# PowerM.net
KiCad netlist of a schematic drawn in Altium Designer
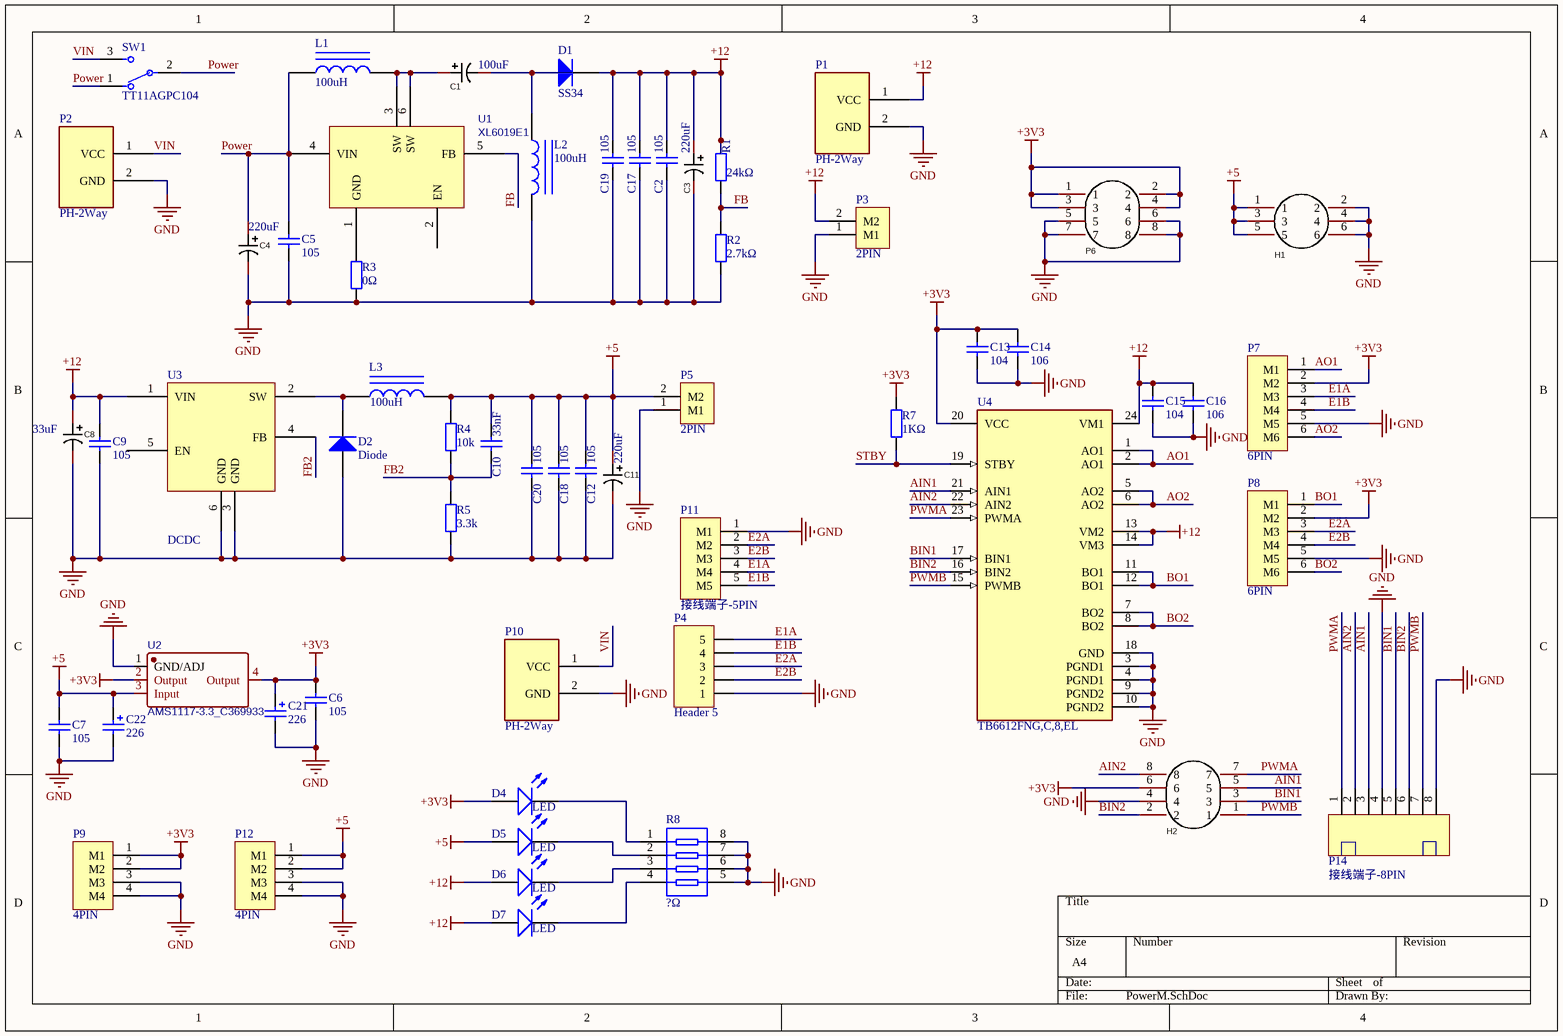
[diagram p0: PowerM.SchDoc]

(export (version "E")
  (design (tool "Eeschema 10.0.6"))
  (components
    (comp (ref "C1")
      (value "100uF")
      (footprint "CAP 5.0*10*12.5")
      (description "插件电容")
      (fields
        (field (name "MANUFACTURER") "MAN YUE(万裕科技)")
        (field (name "MANUFACTURER PART") "ULR107M1CE08TUX0CR")
      )
      (libsource (lib "SFerret") (part "TH_Cap"))
    )
    (comp (ref "C2")
      (value "105")
      (footprint "0603_C")
      (description "贴片电容")
      (libsource (lib "SFerret") (part "SMT_Cap"))
    )
    (comp (ref "C3")
      (value "220uF")
      (footprint "CAP 5.0*10*12.5")
      (description "插件电容")
      (fields
        (field (name "MANUFACTURER") "MAN YUE(万裕科技)")
        (field (name "MANUFACTURER PART") "ULR107M1CE08TUX0CR")
      )
      (libsource (lib "SFerret") (part "TH_Cap"))
    )
    (comp (ref "C4")
      (value "220uF")
      (footprint "CAP 5.0*10*12.5-H")
      (description "插件电容")
      (fields
        (field (name "MANUFACTURER") "MAN YUE(万裕科技)")
        (field (name "MANUFACTURER PART") "ULR107M1CE08TUX0CR")
      )
      (libsource (lib "SFerret") (part "TH_Cap"))
    )
    (comp (ref "C5")
      (value "105")
      (footprint "0603_C")
      (description "贴片电容")
      (libsource (lib "SFerret") (part "SMT_Cap"))
    )
    (comp (ref "C6")
      (value "105")
      (footprint "0603_C")
      (description "贴片电容")
      (libsource (lib "SFerret") (part "SMT_Cap"))
    )
    (comp (ref "C7")
      (value "105")
      (footprint "0603_C")
      (description "贴片电容")
      (libsource (lib "SFerret") (part "SMT_Cap"))
    )
    (comp (ref "C8")
      (value "33uF")
      (footprint "CAP 5.0*10*12.5")
      (description "插件电容")
      (fields
        (field (name "MANUFACTURER") "MAN YUE(万裕科技)")
        (field (name "MANUFACTURER PART") "ULR107M1CE08TUX0CR")
      )
      (libsource (lib "SFerret") (part "TH_Cap"))
    )
    (comp (ref "C9")
      (value "105")
      (footprint "0603_C")
      (description "贴片电容")
      (libsource (lib "SFerret") (part "SMT_Cap"))
    )
    (comp (ref "C10")
      (value "33nF")
      (footprint "0603_C")
      (description "贴片电容")
      (libsource (lib "SFerret") (part "SMT_Cap"))
    )
    (comp (ref "C11")
      (value "220uF")
      (footprint "CAP 5.0*10*12.5-H - GD")
      (description "插件电容")
      (fields
        (field (name "MANUFACTURER") "MAN YUE(万裕科技)")
        (field (name "MANUFACTURER PART") "ULR107M1CE08TUX0CR")
      )
      (libsource (lib "SFerret") (part "TH_Cap"))
    )
    (comp (ref "C12")
      (value "105")
      (footprint "0603_C")
      (description "贴片电容")
      (libsource (lib "SFerret") (part "SMT_Cap"))
    )
    (comp (ref "C13")
      (value "104")
      (footprint "0603_C")
      (description "贴片电容")
      (libsource (lib "SFerret") (part "SMT_Cap"))
    )
    (comp (ref "C14")
      (value "106")
      (footprint "0603_C")
      (description "贴片电容")
      (libsource (lib "SFerret") (part "SMT_Cap"))
    )
    (comp (ref "C15")
      (value "104")
      (footprint "0603_C")
      (description "贴片电容")
      (libsource (lib "SFerret") (part "SMT_Cap"))
    )
    (comp (ref "C16")
      (value "106")
      (footprint "0603_C")
      (description "贴片电容")
      (libsource (lib "SFerret") (part "SMT_Cap"))
    )
    (comp (ref "C17")
      (value "105")
      (footprint "0603_C")
      (description "贴片电容")
      (libsource (lib "SFerret") (part "SMT_Cap"))
    )
    (comp (ref "C18")
      (value "105")
      (footprint "0603_C")
      (description "贴片电容")
      (libsource (lib "SFerret") (part "SMT_Cap"))
    )
    (comp (ref "C19")
      (value "105")
      (footprint "0603_C")
      (description "贴片电容")
      (libsource (lib "SFerret") (part "SMT_Cap"))
    )
    (comp (ref "C20")
      (value "105")
      (footprint "0603_C")
      (description "贴片电容")
      (libsource (lib "SFerret") (part "SMT_Cap"))
    )
    (comp (ref "C21")
      (value "226")
      (footprint "CASE-C_6032")
      (description "钽电容")
      (libsource (lib "SFerret") (part "SMT_Cap_Tantalum"))
    )
    (comp (ref "C22")
      (value "226")
      (footprint "CASE-C_6032")
      (description "钽电容")
      (libsource (lib "SFerret") (part "SMT_Cap_Tantalum"))
    )
    (comp (ref "D1")
      (value "SS34")
      (footprint "SMA(DO-214AC)_S2")
      (description "通用二极管")
      (libsource (lib "SFerret") (part "Diode"))
    )
    (comp (ref "D2")
      (value "Diode")
      (footprint "SMA(DO-214AC)_S2")
      (description "通用二极管")
      (libsource (lib "SFerret") (part "Diode"))
    )
    (comp (ref "D4")
      (value "LED")
      (footprint "0805_LED")
      (description "发光二极管")
      (libsource (lib "SFerret") (part "LED"))
    )
    (comp (ref "D5")
      (value "LED")
      (footprint "0805_LED")
      (description "发光二极管")
      (libsource (lib "SFerret") (part "LED"))
    )
    (comp (ref "D6")
      (value "LED")
      (footprint "0805_LED")
      (description "发光二极管")
      (libsource (lib "SFerret") (part "LED"))
    )
    (comp (ref "D7")
      (value "LED")
      (footprint "0805_LED")
      (description "发光二极管")
      (libsource (lib "SFerret") (part "LED"))
    )
    (comp (ref "H1")
      (value "PH6")
      (footprint "HDR-TH_6P-P2.54-V-M-R2-C3-S2.54-1")
      (fields (field (name "MANUFACTURER") "CJT(长江连接器)") (field (name "MANUFACTURER PART") "A2541WV-2x3P"))
      (libsource (lib "SFerret") (part "PH-6Way-2Row"))
    )
    (comp (ref "H2")
      (value "PH8")
      (footprint "HDR-TH_8P-P2.54-V-R2-C4-S2.54_A2541WV-2X4P")
      (fields (field (name "MANUFACTURER") "CJT(长江连接器)") (field (name "MANUFACTURER PART") "A2541WV-2x4P"))
      (libsource (lib "SFerret") (part "PH-8Way-2Row"))
    )
    (comp (ref "L1")
      (value "100uH")
      (footprint "CDRH127")
      (description "功率电感")
      (libsource (lib "SFerret") (part "SMT_Iud_Power"))
    )
    (comp (ref "L2")
      (value "100uH")
      (footprint "CDRH127")
      (description "功率电感")
      (libsource (lib "SFerret") (part "SMT_Iud_Power"))
    )
    (comp (ref "L3")
      (value "100uH")
      (footprint "CDRH127")
      (description "功率电感")
      (libsource (lib "SFerret") (part "SMT_Iud_Power"))
    )
    (comp (ref "P1") (value "PH-2Way") (footprint "XT30-M") (libsource (lib "SFerret") (part "PH-2Way")))
    (comp (ref "P2") (value "PH-2Way") (footprint "XT30-M") (libsource (lib "SFerret") (part "PH-2Way")))
    (comp (ref "P3") (value "2PIN") (footprint "KF128-2P") (libsource (lib "集大电协1.5") (part "接线端子-2PIN")))
    (comp (ref "P4")
      (value "Header 5")
      (footprint "HDR2.54-WS-5P")
      (description "排针")
      (libsource (lib "SFerret") (part "Header 5"))
    )
    (comp (ref "P5") (value "2PIN") (footprint "KF128-2P") (libsource (lib "集大电协1.5") (part "接线端子-2PIN")))
    (comp (ref "P6")
      (value "PH8")
      (footprint "HDR-TH_8P-P2.54-V-R2-C4-S2.54_A2541WV-2X4P")
      (fields (field (name "MANUFACTURER") "CJT(长江连接器)") (field (name "MANUFACTURER PART") "A2541WV-2x4P"))
      (libsource (lib "SFerret") (part "PH-8Way-2Row"))
    )
    (comp (ref "P7") (value "6PIN") (footprint "PH2.0WS-6P") (libsource (lib "集大电协1.5") (part "接线端子-6PIN")))
    (comp (ref "P8") (value "6PIN") (footprint "PH2.0WS-6P") (libsource (lib "集大电协1.5") (part "接线端子-6PIN")))
    (comp (ref "P9")
      (value "4PIN")
      (footprint "MX1.25WS-4PIN")
      (libsource (lib "集大电协1.5") (part "接线端子-4PIN"))
    )
    (comp (ref "P10")
      (value "PH-2Way")
      (footprint "XH2.54-WS-2P")
      (libsource (lib "SFerret") (part "PH-2Way"))
    )
    (comp (ref "P11")
      (value "接线端子-5PIN")
      (footprint "PH2.0-WS-5P")
      (libsource (lib "集大电协1.5") (part "接线端子-5PIN"))
    )
    (comp (ref "P12")
      (value "4PIN")
      (footprint "MX1.25WS-4PIN")
      (libsource (lib "集大电协1.5") (part "接线端子-4PIN"))
    )
    (comp (ref "P14")
      (value "接线端子-8PIN")
      (footprint "MX1.25WS-8P")
      (libsource (lib "集大电协1.5") (part "接线端子-8PIN"))
    )
    (comp (ref "R1")
      (value "24kΩ")
      (footprint "0603_R")
      (description "贴片电阻")
      (libsource (lib "SFerret") (part "SMT_Res"))
    )
    (comp (ref "R2")
      (value "2.7kΩ")
      (footprint "0603_R")
      (description "贴片电阻")
      (libsource (lib "SFerret") (part "SMT_Res"))
    )
    (comp (ref "R3")
      (value "0Ω")
      (footprint "1206_R")
      (description "贴片电阻")
      (libsource (lib "SFerret") (part "SMT_Res"))
    )
    (comp (ref "R4")
      (value "10k")
      (footprint "0603_R")
      (description "贴片电阻")
      (libsource (lib "SFerret") (part "SMT_Res"))
    )
    (comp (ref "R5")
      (value "3.3k")
      (footprint "0603_R")
      (description "贴片电阻")
      (libsource (lib "SFerret") (part "SMT_Res"))
    )
    (comp (ref "R7")
      (value "1KΩ")
      (footprint "0603_R")
      (description "贴片电阻")
      (libsource (lib "SFerret") (part "SMT_Res"))
    )
    (comp (ref "R8")
      (value "?Ω")
      (footprint "0603_Rx4")
      (description "贴片排阻")
      (libsource (lib "SFerret") (part "SMT_Res-4"))
    )
    (comp (ref "SW1")
      (value "TT11AGPC104")
      (footprint "FP-TT11AGPC104-MFG")
      (description "SWITCH TOGGLE SPST 0.4VA 20V")
      (libsource (lib "Altium Content Vault") (part "52c419afdc2a387c7d548259a9aeefb"))
    )
    (comp (ref "U1")
      (value "XL6019E1")
      (footprint "TO-263-5_L10.2-W9.9-P1.70-LS14.4-TL")
      (description "宽输入DCDC升降压管理芯片")
      (fields (field (name "BOM_SUPPLIER PART") "C73018"))
      (libsource (lib "SFerret") (part "XL6019E1"))
    )
    (comp (ref "U2")
      (value "AMS1117-3.3_C369933")
      (footprint "SOT-223-4_L6.5-W3.5-P2.30-LS7.0-BR")
      (fields
        (field (name "BOM_SUPPLIER PART") "C369933")
        (field (name "BOM_MANUFACTURER PART") "AMS1117-3.3")
        (field (name "CONTRIBUTOR") "LCSC")
      )
      (libsource (lib "Schlib1") (part "AMS1117-3.3_C369933"))
    )
    (comp (ref "U3")
      (value "DCDC")
      (footprint "TO-252-XL")
      (description "宽输入DCDC升降压管理芯片（Buck）")
      (libsource (lib "SFerret") (part "XL7015"))
    )
    (comp (ref "U4")
      (value "TB6612FNG,C,8,EL")
      (footprint "FP-SSOP24-P-300-0_65A-IPC_A")
      (description "IC MOTOR DRIVER 2.7V-5.5V 24SSOP")
      (libsource (lib "Altium Content Vault") (part "0e8a2fe7f3780dc9c50f4d41012bdec"))
    )
  )
  (nets
    (net (code "1") (name "+3V3") (class "Default")
      (node (ref "C13") (pin "2") (pinfunction "2_2") (pintype "passive"))
      (node (ref "C14") (pin "2") (pinfunction "2_2") (pintype "passive"))
      (node (ref "C21") (pin "1") (pinfunction "1_1") (pintype "passive"))
      (node (ref "C6") (pin "2") (pinfunction "2_2") (pintype "passive"))
      (node (ref "D4") (pin "A") (pinfunction "A_A") (pintype "passive"))
      (node (ref "H2") (pin "6") (pinfunction "6_6") (pintype "passive"))
      (node (ref "P6") (pin "1") (pinfunction "1_1") (pintype "passive"))
      (node (ref "P6") (pin "2") (pinfunction "2_2") (pintype "passive"))
      (node (ref "P6") (pin "3") (pinfunction "3_3") (pintype "passive"))
      (node (ref "P6") (pin "4") (pinfunction "4_4") (pintype "passive"))
      (node (ref "P7") (pin "2") (pinfunction "M2_2") (pintype "passive"))
      (node (ref "P8") (pin "2") (pinfunction "M2_2") (pintype "passive"))
      (node (ref "P9") (pin "1") (pinfunction "M1_1") (pintype "passive"))
      (node (ref "P9") (pin "2") (pinfunction "M2_2") (pintype "passive"))
      (node (ref "R7") (pin "2") (pinfunction "2_2") (pintype "passive"))
      (node (ref "U2") (pin "2") (pinfunction "Output_2") (pintype "passive"))
      (node (ref "U2") (pin "4") (pinfunction "Output_4") (pintype "passive"))
      (node (ref "U4") (pin "20") (pinfunction "VCC_20") (pintype "power_in"))
    )
    (net (code "2") (name "+5") (class "Default")
      (node (ref "C10") (pin "1") (pinfunction "1_1") (pintype "passive"))
      (node (ref "C11") (pin "1") (pinfunction "1_1") (pintype "passive"))
      (node (ref "C12") (pin "2") (pinfunction "2_2") (pintype "passive"))
      (node (ref "C18") (pin "2") (pinfunction "2_2") (pintype "passive"))
      (node (ref "C20") (pin "2") (pinfunction "2_2") (pintype "passive"))
      (node (ref "C22") (pin "1") (pinfunction "1_1") (pintype "passive"))
      (node (ref "C7") (pin "2") (pinfunction "2_2") (pintype "passive"))
      (node (ref "D5") (pin "A") (pinfunction "A_A") (pintype "passive"))
      (node (ref "H1") (pin "1") (pinfunction "1_1") (pintype "passive"))
      (node (ref "H1") (pin "3") (pinfunction "3_3") (pintype "passive"))
      (node (ref "H1") (pin "5") (pinfunction "5_5") (pintype "passive"))
      (node (ref "L3") (pin "2") (pinfunction "2_2") (pintype "passive"))
      (node (ref "P12") (pin "1") (pinfunction "M1_1") (pintype "passive"))
      (node (ref "P12") (pin "2") (pinfunction "M2_2") (pintype "passive"))
      (node (ref "P5") (pin "2") (pinfunction "M2_2") (pintype "passive"))
      (node (ref "R4") (pin "2") (pinfunction "2_2") (pintype "passive"))
      (node (ref "U2") (pin "3") (pinfunction "Input_3") (pintype "passive"))
    )
    (net (code "3") (name "+12") (class "Default")
      (node (ref "C15") (pin "2") (pinfunction "2_2") (pintype "passive"))
      (node (ref "C16") (pin "2") (pinfunction "2_2") (pintype "passive"))
      (node (ref "C17") (pin "2") (pinfunction "2_2") (pintype "passive"))
      (node (ref "C19") (pin "2") (pinfunction "2_2") (pintype "passive"))
      (node (ref "C2") (pin "2") (pinfunction "2_2") (pintype "passive"))
      (node (ref "C3") (pin "1") (pinfunction "1_1") (pintype "passive"))
      (node (ref "C8") (pin "1") (pinfunction "1_1") (pintype "passive"))
      (node (ref "C9") (pin "2") (pinfunction "2_2") (pintype "passive"))
      (node (ref "D1") (pin "2") (pinfunction "K_2") (pintype "passive"))
      (node (ref "D6") (pin "A") (pinfunction "A_A") (pintype "passive"))
      (node (ref "D7") (pin "A") (pinfunction "A_A") (pintype "passive"))
      (node (ref "P1") (pin "1") (pinfunction "VCC_1") (pintype "passive"))
      (node (ref "P3") (pin "2") (pinfunction "M2_2") (pintype "passive"))
      (node (ref "R1") (pin "2") (pinfunction "2_2") (pintype "passive"))
      (node (ref "U3") (pin "1") (pinfunction "VIN_1") (pintype "passive"))
      (node (ref "U4") (pin "13") (pinfunction "VM2_13") (pintype "power_in"))
      (node (ref "U4") (pin "14") (pinfunction "VM3_14") (pintype "power_in"))
      (node (ref "U4") (pin "24") (pinfunction "VM1_24") (pintype "power_in"))
    )
    (net (code "4") (name "/AIN1") (class "Default")
      (node (ref "H2") (pin "5") (pinfunction "5_5") (pintype "passive"))
      (node (ref "P14") (pin "3") (pinfunction "3_3") (pintype "passive"))
      (node (ref "U4") (pin "21") (pinfunction "AIN1_21") (pintype "input"))
    )
    (net (code "5") (name "/AIN2") (class "Default")
      (node (ref "H2") (pin "8") (pinfunction "8_8") (pintype "passive"))
      (node (ref "P14") (pin "2") (pinfunction "2_2") (pintype "passive"))
      (node (ref "U4") (pin "22") (pinfunction "AIN2_22") (pintype "input"))
    )
    (net (code "6") (name "/AO1") (class "Default")
      (node (ref "P7") (pin "1") (pinfunction "M1_1") (pintype "passive"))
      (node (ref "U4") (pin "1") (pinfunction "AO1_1") (pintype "passive"))
      (node (ref "U4") (pin "2") (pinfunction "AO1_2") (pintype "passive"))
    )
    (net (code "7") (name "/AO2") (class "Default")
      (node (ref "P7") (pin "6") (pinfunction "M6_6") (pintype "passive"))
      (node (ref "U4") (pin "5") (pinfunction "AO2_5") (pintype "passive"))
      (node (ref "U4") (pin "6") (pinfunction "AO2_6") (pintype "passive"))
    )
    (net (code "8") (name "/BIN1") (class "Default")
      (node (ref "H2") (pin "3") (pinfunction "3_3") (pintype "passive"))
      (node (ref "P14") (pin "5") (pinfunction "5_5") (pintype "passive"))
      (node (ref "U4") (pin "17") (pinfunction "BIN1_17") (pintype "input"))
    )
    (net (code "9") (name "/BIN2") (class "Default")
      (node (ref "H2") (pin "2") (pinfunction "2_2") (pintype "passive"))
      (node (ref "P14") (pin "6") (pinfunction "6_6") (pintype "passive"))
      (node (ref "U4") (pin "16") (pinfunction "BIN2_16") (pintype "input"))
    )
    (net (code "10") (name "/BO1") (class "Default")
      (node (ref "P8") (pin "1") (pinfunction "M1_1") (pintype "passive"))
      (node (ref "U4") (pin "11") (pinfunction "BO1_11") (pintype "passive"))
      (node (ref "U4") (pin "12") (pinfunction "BO1_12") (pintype "passive"))
    )
    (net (code "11") (name "/BO2") (class "Default")
      (node (ref "P8") (pin "6") (pinfunction "M6_6") (pintype "passive"))
      (node (ref "U4") (pin "7") (pinfunction "BO2_7") (pintype "passive"))
      (node (ref "U4") (pin "8") (pinfunction "BO2_8") (pintype "passive"))
    )
    (net (code "12") (name "/E1A") (class "Default")
      (node (ref "P11") (pin "4") (pinfunction "M4_4") (pintype "passive"))
      (node (ref "P4") (pin "5") (pinfunction "5_5") (pintype "passive"))
      (node (ref "P7") (pin "3") (pinfunction "M3_3") (pintype "passive"))
    )
    (net (code "13") (name "/E1B") (class "Default")
      (node (ref "P11") (pin "5") (pinfunction "M5_5") (pintype "passive"))
      (node (ref "P4") (pin "4") (pinfunction "4_4") (pintype "passive"))
      (node (ref "P7") (pin "4") (pinfunction "M4_4") (pintype "passive"))
    )
    (net (code "14") (name "/E2A") (class "Default")
      (node (ref "P11") (pin "2") (pinfunction "M2_2") (pintype "passive"))
      (node (ref "P4") (pin "3") (pinfunction "3_3") (pintype "passive"))
      (node (ref "P8") (pin "3") (pinfunction "M3_3") (pintype "passive"))
    )
    (net (code "15") (name "/E2B") (class "Default")
      (node (ref "P11") (pin "3") (pinfunction "M3_3") (pintype "passive"))
      (node (ref "P4") (pin "2") (pinfunction "2_2") (pintype "passive"))
      (node (ref "P8") (pin "4") (pinfunction "M4_4") (pintype "passive"))
    )
    (net (code "16") (name "/FB") (class "Default")
      (node (ref "R1") (pin "1") (pinfunction "1_1") (pintype "passive"))
      (node (ref "R2") (pin "2") (pinfunction "2_2") (pintype "passive"))
      (node (ref "U1") (pin "5") (pinfunction "FB_5") (pintype "passive"))
    )
    (net (code "17") (name "/FB2") (class "Default")
      (node (ref "C10") (pin "2") (pinfunction "2_2") (pintype "passive"))
      (node (ref "R4") (pin "1") (pinfunction "1_1") (pintype "passive"))
      (node (ref "R5") (pin "2") (pinfunction "2_2") (pintype "passive"))
      (node (ref "U3") (pin "4") (pinfunction "FB_4") (pintype "passive"))
    )
    (net (code "18") (name "/PWMA") (class "Default")
      (node (ref "H2") (pin "7") (pinfunction "7_7") (pintype "passive"))
      (node (ref "P14") (pin "1") (pinfunction "1_1") (pintype "passive"))
      (node (ref "U4") (pin "23") (pinfunction "PWMA_23") (pintype "input"))
    )
    (net (code "19") (name "/PWMB") (class "Default")
      (node (ref "H2") (pin "1") (pinfunction "1_1") (pintype "passive"))
      (node (ref "P14") (pin "7") (pinfunction "7_7") (pintype "passive"))
      (node (ref "U4") (pin "15") (pinfunction "PWMB_15") (pintype "input"))
    )
    (net (code "20") (name "/Power") (class "Default")
      (node (ref "C4") (pin "1") (pinfunction "1_1") (pintype "passive"))
      (node (ref "C5") (pin "2") (pinfunction "2_2") (pintype "passive"))
      (node (ref "L1") (pin "1") (pinfunction "1_1") (pintype "passive"))
      (node (ref "SW1") (pin "1") (pinfunction "1_1") (pintype "passive"))
      (node (ref "SW1") (pin "2") (pinfunction "2_2") (pintype "passive"))
      (node (ref "U1") (pin "4") (pinfunction "VIN_4") (pintype "passive"))
    )
    (net (code "21") (name "/STBY") (class "Default")
      (node (ref "R7") (pin "1") (pinfunction "1_1") (pintype "passive"))
      (node (ref "U4") (pin "19") (pinfunction "STBY_19") (pintype "input"))
    )
    (net (code "22") (name "/VIN") (class "Default")
      (node (ref "P10") (pin "1") (pinfunction "VCC_1") (pintype "passive"))
      (node (ref "P2") (pin "1") (pinfunction "VCC_1") (pintype "passive"))
      (node (ref "SW1") (pin "3") (pinfunction "3_3") (pintype "passive"))
    )
    (net (code "23") (name "GND") (class "Default")
      (node (ref "C11") (pin "2") (pinfunction "2_2") (pintype "passive"))
      (node (ref "C12") (pin "1") (pinfunction "1_1") (pintype "passive"))
      (node (ref "C13") (pin "1") (pinfunction "1_1") (pintype "passive"))
      (node (ref "C14") (pin "1") (pinfunction "1_1") (pintype "passive"))
      (node (ref "C15") (pin "1") (pinfunction "1_1") (pintype "passive"))
      (node (ref "C16") (pin "1") (pinfunction "1_1") (pintype "passive"))
      (node (ref "C17") (pin "1") (pinfunction "1_1") (pintype "passive"))
      (node (ref "C18") (pin "1") (pinfunction "1_1") (pintype "passive"))
      (node (ref "C19") (pin "1") (pinfunction "1_1") (pintype "passive"))
      (node (ref "C2") (pin "1") (pinfunction "1_1") (pintype "passive"))
      (node (ref "C20") (pin "1") (pinfunction "1_1") (pintype "passive"))
      (node (ref "C21") (pin "2") (pinfunction "2_2") (pintype "passive"))
      (node (ref "C22") (pin "2") (pinfunction "2_2") (pintype "passive"))
      (node (ref "C3") (pin "2") (pinfunction "2_2") (pintype "passive"))
      (node (ref "C4") (pin "2") (pinfunction "2_2") (pintype "passive"))
      (node (ref "C5") (pin "1") (pinfunction "1_1") (pintype "passive"))
      (node (ref "C6") (pin "1") (pinfunction "1_1") (pintype "passive"))
      (node (ref "C7") (pin "1") (pinfunction "1_1") (pintype "passive"))
      (node (ref "C8") (pin "2") (pinfunction "2_2") (pintype "passive"))
      (node (ref "C9") (pin "1") (pinfunction "1_1") (pintype "passive"))
      (node (ref "D2") (pin "1") (pinfunction "A_1") (pintype "passive"))
      (node (ref "H1") (pin "2") (pinfunction "2_2") (pintype "passive"))
      (node (ref "H1") (pin "4") (pinfunction "4_4") (pintype "passive"))
      (node (ref "H1") (pin "6") (pinfunction "6_6") (pintype "passive"))
      (node (ref "H2") (pin "4") (pinfunction "4_4") (pintype "passive"))
      (node (ref "L2") (pin "2") (pinfunction "2_2") (pintype "passive"))
      (node (ref "P1") (pin "2") (pinfunction "GND_2") (pintype "passive"))
      (node (ref "P10") (pin "2") (pinfunction "GND_2") (pintype "passive"))
      (node (ref "P11") (pin "1") (pinfunction "M1_1") (pintype "passive"))
      (node (ref "P12") (pin "3") (pinfunction "M3_3") (pintype "passive"))
      (node (ref "P12") (pin "4") (pinfunction "M4_4") (pintype "passive"))
      (node (ref "P14") (pin "4") (pinfunction "4_4") (pintype "passive"))
      (node (ref "P14") (pin "8") (pinfunction "8_8") (pintype "passive"))
      (node (ref "P2") (pin "2") (pinfunction "GND_2") (pintype "passive"))
      (node (ref "P3") (pin "1") (pinfunction "M1_1") (pintype "passive"))
      (node (ref "P4") (pin "1") (pinfunction "1_1") (pintype "passive"))
      (node (ref "P5") (pin "1") (pinfunction "M1_1") (pintype "passive"))
      (node (ref "P6") (pin "5") (pinfunction "5_5") (pintype "passive"))
      (node (ref "P6") (pin "6") (pinfunction "6_6") (pintype "passive"))
      (node (ref "P6") (pin "7") (pinfunction "7_7") (pintype "passive"))
      (node (ref "P6") (pin "8") (pinfunction "8_8") (pintype "passive"))
      (node (ref "P7") (pin "5") (pinfunction "M5_5") (pintype "passive"))
      (node (ref "P8") (pin "5") (pinfunction "M5_5") (pintype "passive"))
      (node (ref "P9") (pin "3") (pinfunction "M3_3") (pintype "passive"))
      (node (ref "P9") (pin "4") (pinfunction "M4_4") (pintype "passive"))
      (node (ref "R2") (pin "1") (pinfunction "1_1") (pintype "passive"))
      (node (ref "R3") (pin "1") (pinfunction "1_1") (pintype "passive"))
      (node (ref "R5") (pin "1") (pinfunction "1_1") (pintype "passive"))
      (node (ref "R8") (pin "5") (pinfunction "5_5") (pintype "passive"))
      (node (ref "R8") (pin "6") (pinfunction "6_6") (pintype "passive"))
      (node (ref "R8") (pin "7") (pinfunction "7_7") (pintype "passive"))
      (node (ref "R8") (pin "8") (pinfunction "8_8") (pintype "passive"))
      (node (ref "U2") (pin "1") (pinfunction "GND/ADJ_1") (pintype "passive"))
      (node (ref "U3") (pin "3") (pinfunction "GND_3") (pintype "passive"))
      (node (ref "U3") (pin "6") (pinfunction "GND_6") (pintype "passive"))
      (node (ref "U4") (pin "10") (pinfunction "PGND2_10") (pintype "power_in"))
      (node (ref "U4") (pin "18") (pinfunction "GND_18") (pintype "power_in"))
      (node (ref "U4") (pin "3") (pinfunction "PGND1_3") (pintype "power_in"))
      (node (ref "U4") (pin "4") (pinfunction "PGND1_4") (pintype "power_in"))
      (node (ref "U4") (pin "9") (pinfunction "PGND2_9") (pintype "power_in"))
    )
    (net (code "24") (name "Net-(C1-Pad1)") (class "Default")
      (node (ref "C1") (pin "1") (pinfunction "1_1") (pintype "passive"))
      (node (ref "L1") (pin "2") (pinfunction "2_2") (pintype "passive"))
      (node (ref "U1") (pin "3") (pinfunction "SW_3") (pintype "passive"))
      (node (ref "U1") (pin "6") (pinfunction "SW_6") (pintype "passive"))
    )
    (net (code "25") (name "Net-(D1-A)") (class "Default")
      (node (ref "C1") (pin "2") (pinfunction "2_2") (pintype "passive"))
      (node (ref "D1") (pin "1") (pinfunction "A_1") (pintype "passive"))
      (node (ref "L2") (pin "1") (pinfunction "1_1") (pintype "passive"))
    )
    (net (code "26") (name "Net-(D2-K)") (class "Default")
      (node (ref "D2") (pin "2") (pinfunction "K_2") (pintype "passive"))
      (node (ref "L3") (pin "1") (pinfunction "1_1") (pintype "passive"))
      (node (ref "U3") (pin "2") (pinfunction "SW_2") (pintype "passive"))
    )
    (net (code "27") (name "Net-(D4-PadK)") (class "Default")
      (node (ref "D4") (pin "K") (pinfunction "K_K") (pintype "passive"))
      (node (ref "R8") (pin "1") (pinfunction "1_1") (pintype "passive"))
    )
    (net (code "28") (name "Net-(D5-PadK)") (class "Default")
      (node (ref "D5") (pin "K") (pinfunction "K_K") (pintype "passive"))
      (node (ref "R8") (pin "2") (pinfunction "2_2") (pintype "passive"))
    )
    (net (code "29") (name "Net-(D6-PadK)") (class "Default")
      (node (ref "D6") (pin "K") (pinfunction "K_K") (pintype "passive"))
      (node (ref "R8") (pin "3") (pinfunction "3_3") (pintype "passive"))
    )
    (net (code "30") (name "Net-(D7-PadK)") (class "Default")
      (node (ref "D7") (pin "K") (pinfunction "K_K") (pintype "passive"))
      (node (ref "R8") (pin "4") (pinfunction "4_4") (pintype "passive"))
    )
    (net (code "31") (name "Net-(U1-GND)") (class "Default")
      (node (ref "R3") (pin "2") (pinfunction "2_2") (pintype "passive"))
      (node (ref "U1") (pin "1") (pinfunction "GND_1") (pintype "passive"))
    )
    (net (code "32") (name "unconnected-(U1-EN-Pad2)") (class "Default")
      (node (ref "U1") (pin "2") (pinfunction "EN_2") (pintype "passive"))
    )
    (net (code "33") (name "unconnected-(U3-EN-Pad5)") (class "Default")
      (node (ref "U3") (pin "5") (pinfunction "EN_5") (pintype "passive"))
    )
  )
)
